# main.net
KiCad netlist of a schematic drawn in Altium Designer
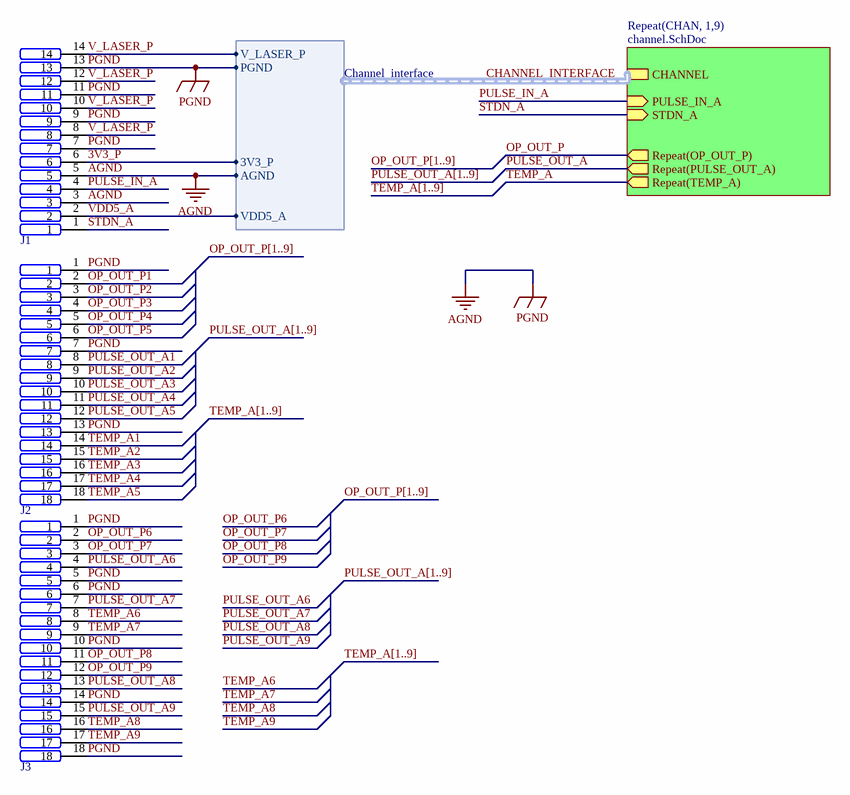
[diagram p0: main.SchDoc]

(export (version "E")
  (design (tool "Eeschema 10.0.6"))
  (components
    (comp (ref "J1")
      (value "FPC_conn")
      (footprint "FPC_connector_14_1mm")
      (description "Connector FPC, 14 pin, 1mm pitch")
      (libsource (lib "ld_harness") (part "FPC_connector_1mm_14"))
    )
    (comp (ref "J2")
      (value "FPC_conn")
      (footprint "FPC_connector_18_0.5")
      (description "Connector FPC, 18 pin, 0.5mm pitch")
      (libsource (lib "ld_harness") (part "FPC_connector"))
    )
    (comp (ref "J3")
      (value "FPC_conn")
      (footprint "FPC_connector_18_0.5")
      (description "Connector FPC, 18 pin, 0.5mm pitch")
      (libsource (lib "ld_harness") (part "FPC_connector"))
    )
  )
  (nets
    (net (code "2") (name "/3V3_P") (class "Default")
      (node (ref "J1") (pin "6") (pinfunction "6_6") (pintype "passive"))
    )
    (net (code "5") (name "/OP_OUT_P1") (class "Default")
      (node (ref "J2") (pin "2") (pinfunction "2_2") (pintype "passive"))
    )
    (net (code "6") (name "/OP_OUT_P2") (class "Default")
      (node (ref "J2") (pin "3") (pinfunction "3_3") (pintype "passive"))
    )
    (net (code "7") (name "/OP_OUT_P3") (class "Default")
      (node (ref "J2") (pin "4") (pinfunction "4_4") (pintype "passive"))
    )
    (net (code "8") (name "/OP_OUT_P4") (class "Default")
      (node (ref "J2") (pin "5") (pinfunction "5_5") (pintype "passive"))
    )
    (net (code "9") (name "/OP_OUT_P5") (class "Default")
      (node (ref "J2") (pin "6") (pinfunction "6_6") (pintype "passive"))
    )
    (net (code "10") (name "/OP_OUT_P6") (class "Default")
      (node (ref "J3") (pin "2") (pinfunction "2_2") (pintype "passive"))
    )
    (net (code "11") (name "/OP_OUT_P7") (class "Default")
      (node (ref "J3") (pin "3") (pinfunction "3_3") (pintype "passive"))
    )
    (net (code "12") (name "/OP_OUT_P8") (class "Default")
      (node (ref "J3") (pin "11") (pinfunction "11_11") (pintype "passive"))
    )
    (net (code "13") (name "/OP_OUT_P9") (class "Default")
      (node (ref "J3") (pin "12") (pinfunction "12_12") (pintype "passive"))
    )
    (net (code "15") (name "/PULSE_IN_A") (class "Default")
      (node (ref "J1") (pin "4") (pinfunction "4_4") (pintype "passive"))
    )
    (net (code "17") (name "/PULSE_OUT_A1") (class "Default")
      (node (ref "J2") (pin "8") (pinfunction "8_8") (pintype "passive"))
    )
    (net (code "18") (name "/PULSE_OUT_A2") (class "Default")
      (node (ref "J2") (pin "9") (pinfunction "9_9") (pintype "passive"))
    )
    (net (code "19") (name "/PULSE_OUT_A3") (class "Default")
      (node (ref "J2") (pin "10") (pinfunction "10_10") (pintype "passive"))
    )
    (net (code "20") (name "/PULSE_OUT_A4") (class "Default")
      (node (ref "J2") (pin "11") (pinfunction "11_11") (pintype "passive"))
    )
    (net (code "21") (name "/PULSE_OUT_A5") (class "Default")
      (node (ref "J2") (pin "12") (pinfunction "12_12") (pintype "passive"))
    )
    (net (code "22") (name "/PULSE_OUT_A6") (class "Default")
      (node (ref "J3") (pin "4") (pinfunction "4_4") (pintype "passive"))
    )
    (net (code "23") (name "/PULSE_OUT_A7") (class "Default")
      (node (ref "J3") (pin "7") (pinfunction "7_7") (pintype "passive"))
    )
    (net (code "24") (name "/PULSE_OUT_A8") (class "Default")
      (node (ref "J3") (pin "13") (pinfunction "13_13") (pintype "passive"))
    )
    (net (code "25") (name "/PULSE_OUT_A9") (class "Default")
      (node (ref "J3") (pin "15") (pinfunction "15_15") (pintype "passive"))
    )
    (net (code "27") (name "/STDN_A") (class "Default")
      (node (ref "J1") (pin "1") (pinfunction "1_1") (pintype "passive"))
    )
    (net (code "29") (name "/TEMP_A1") (class "Default")
      (node (ref "J2") (pin "14") (pinfunction "14_14") (pintype "passive"))
    )
    (net (code "30") (name "/TEMP_A2") (class "Default")
      (node (ref "J2") (pin "15") (pinfunction "15_15") (pintype "passive"))
    )
    (net (code "31") (name "/TEMP_A3") (class "Default")
      (node (ref "J2") (pin "16") (pinfunction "16_16") (pintype "passive"))
    )
    (net (code "32") (name "/TEMP_A4") (class "Default")
      (node (ref "J2") (pin "17") (pinfunction "17_17") (pintype "passive"))
    )
    (net (code "33") (name "/TEMP_A5") (class "Default")
      (node (ref "J2") (pin "18") (pinfunction "18_18") (pintype "passive"))
    )
    (net (code "34") (name "/TEMP_A6") (class "Default")
      (node (ref "J3") (pin "8") (pinfunction "8_8") (pintype "passive"))
    )
    (net (code "35") (name "/TEMP_A7") (class "Default")
      (node (ref "J3") (pin "9") (pinfunction "9_9") (pintype "passive"))
    )
    (net (code "36") (name "/TEMP_A8") (class "Default")
      (node (ref "J3") (pin "16") (pinfunction "16_16") (pintype "passive"))
    )
    (net (code "37") (name "/TEMP_A9") (class "Default")
      (node (ref "J3") (pin "17") (pinfunction "17_17") (pintype "passive"))
    )
    (net (code "39") (name "/VDD5_A") (class "Default")
      (node (ref "J1") (pin "2") (pinfunction "2_2") (pintype "passive"))
    )
    (net (code "40") (name "/V_LASER_P") (class "Default")
      (node (ref "J1") (pin "10") (pinfunction "10_10") (pintype "passive"))
      (node (ref "J1") (pin "12") (pinfunction "12_12") (pintype "passive"))
      (node (ref "J1") (pin "14") (pinfunction "14_14") (pintype "passive"))
      (node (ref "J1") (pin "8") (pinfunction "8_8") (pintype "passive"))
    )
    (net (code "41") (name "AGND") (class "Default")
      (node (ref "J1") (pin "11") (pinfunction "11_11") (pintype "passive"))
      (node (ref "J1") (pin "13") (pinfunction "13_13") (pintype "passive"))
      (node (ref "J1") (pin "3") (pinfunction "3_3") (pintype "passive"))
      (node (ref "J1") (pin "5") (pinfunction "5_5") (pintype "passive"))
      (node (ref "J1") (pin "7") (pinfunction "7_7") (pintype "passive"))
      (node (ref "J1") (pin "9") (pinfunction "9_9") (pintype "passive"))
      (node (ref "J2") (pin "1") (pinfunction "1_1") (pintype "passive"))
      (node (ref "J2") (pin "13") (pinfunction "13_13") (pintype "passive"))
      (node (ref "J2") (pin "7") (pinfunction "7_7") (pintype "passive"))
      (node (ref "J3") (pin "1") (pinfunction "1_1") (pintype "passive"))
      (node (ref "J3") (pin "10") (pinfunction "10_10") (pintype "passive"))
      (node (ref "J3") (pin "14") (pinfunction "14_14") (pintype "passive"))
      (node (ref "J3") (pin "18") (pinfunction "18_18") (pintype "passive"))
      (node (ref "J3") (pin "5") (pinfunction "5_5") (pintype "passive"))
      (node (ref "J3") (pin "6") (pinfunction "6_6") (pintype "passive"))
    )
  )
)
